# Intelligent_Agriculture.net
KiCad netlist of a schematic drawn in Altium Designer
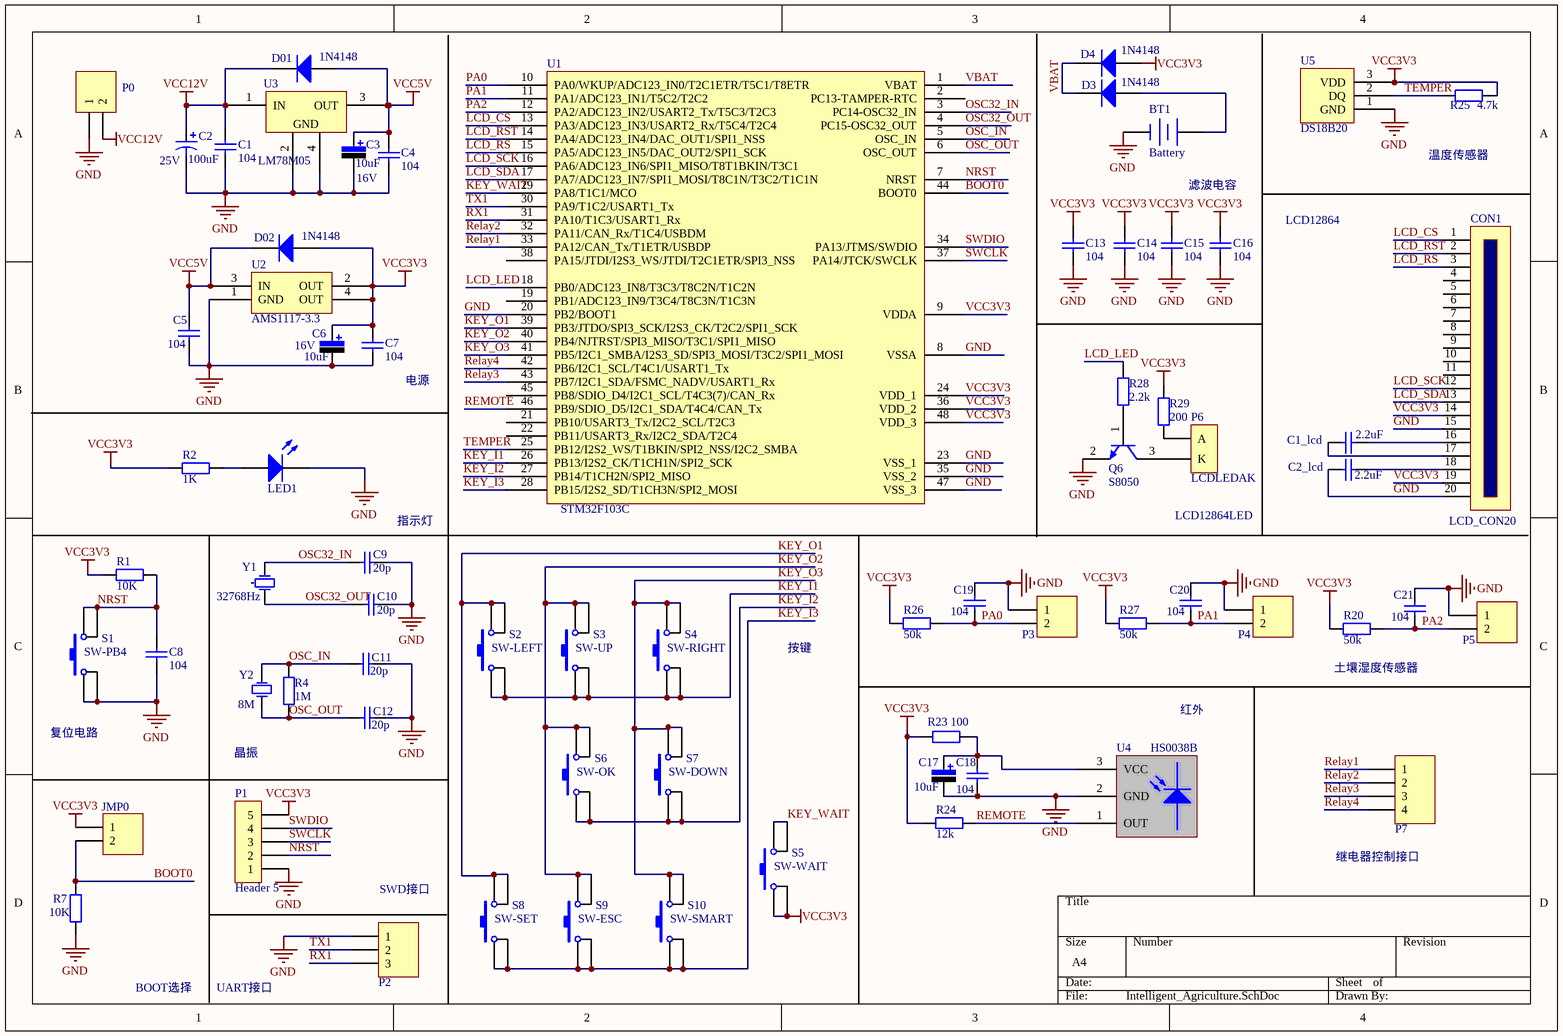
[diagram p0: Intelligent_Agriculture.SchDoc]

(export (version "E")
  (design (tool "Eeschema 10.0.6"))
  (components
    (comp (ref "BT1")
      (value "Battery")
      (footprint "CR1220")
      (description "备份电池")
      (fields (field (name "PUBLISHER") "Altium Limited"))
      (libsource (lib "fszhang") (part "Battery"))
    )
    (comp (ref "C1")
      (value "104")
      (footprint "C-RAD-0805")
      (description "无极性电容")
      (fields (field (name "Comment") "Cap") (field (name "PUBLISHER") "Altium Limited"))
      (libsource (lib "fszhang") (part "Cap"))
    )
    (comp (ref "C1_lcd")
      (value "2.2uF")
      (footprint "C-RAD-0805")
      (description "无极性电容")
      (fields (field (name "Comment") "Cap") (field (name "PUBLISHER") "Altium Limited"))
      (libsource (lib "fszhang") (part "Cap"))
    )
    (comp (ref "C2")
      (value "100uF")
      (footprint "C-RB-2.54")
      (description "电解电容")
      (fields
        (field (name "VOL") "25V")
        (field (name "Comment") "Cap Pol1")
        (field (name "PUBLISHER") "Altium Limited")
      )
      (libsource (lib "Miscellaneous Devices") (part "Cap Pol1"))
    )
    (comp (ref "C2_lcd")
      (value "2.2uF")
      (footprint "C-RAD-0805")
      (description "无极性电容")
      (fields (field (name "Comment") "Cap") (field (name "PUBLISHER") "Altium Limited"))
      (libsource (lib "fszhang") (part "Cap"))
    )
    (comp (ref "C3")
      (value "10uF")
      (footprint "CAP-3528")
      (description "钽电容")
      (fields
        (field (name "VOL") "16V")
        (field (name "Comment") "Cap Pol")
        (field (name "PUBLISHER") "Altium Limited")
      )
      (libsource (lib "fszhang") (part "Cap Pol"))
    )
    (comp (ref "C4")
      (value "104")
      (footprint "C-RAD-0805")
      (description "无极性电容")
      (fields (field (name "Comment") "Cap") (field (name "PUBLISHER") "Altium Limited"))
      (libsource (lib "fszhang") (part "Cap"))
    )
    (comp (ref "C5")
      (value "104")
      (footprint "C-RAD-0805")
      (description "无极性电容")
      (fields (field (name "Comment") "Cap") (field (name "PUBLISHER") "Altium Limited"))
      (libsource (lib "fszhang") (part "Cap"))
    )
    (comp (ref "C6")
      (value "10uF")
      (footprint "CAP-3528")
      (description "钽电容")
      (fields
        (field (name "VOL") "16V")
        (field (name "Comment") "Cap Pol")
        (field (name "PUBLISHER") "Altium Limited")
      )
      (libsource (lib "fszhang") (part "Cap Pol"))
    )
    (comp (ref "C7")
      (value "104")
      (footprint "C-RAD-0805")
      (description "无极性电容")
      (fields (field (name "Comment") "Cap") (field (name "PUBLISHER") "Altium Limited"))
      (libsource (lib "fszhang") (part "Cap"))
    )
    (comp (ref "C8")
      (value "104")
      (footprint "C-RAD-0805")
      (description "无极性电容")
      (fields (field (name "Comment") "Cap") (field (name "PUBLISHER") "Altium Limited"))
      (libsource (lib "fszhang") (part "Cap"))
    )
    (comp (ref "C9")
      (value "20p")
      (footprint "C-RAD-0805")
      (description "无极性电容")
      (fields (field (name "Comment") "Cap") (field (name "PUBLISHER") "Altium Limited"))
      (libsource (lib "fszhang") (part "Cap"))
    )
    (comp (ref "C10")
      (value "20p")
      (footprint "C-RAD-0805")
      (description "无极性电容")
      (fields (field (name "Comment") "Cap") (field (name "PUBLISHER") "Altium Limited"))
      (libsource (lib "fszhang") (part "Cap"))
    )
    (comp (ref "C11")
      (value "20p")
      (footprint "C-RAD-0805")
      (description "无极性电容")
      (fields (field (name "Comment") "Cap") (field (name "PUBLISHER") "Altium Limited"))
      (libsource (lib "fszhang") (part "Cap"))
    )
    (comp (ref "C12")
      (value "20p")
      (footprint "C-RAD-0805")
      (description "无极性电容")
      (fields (field (name "Comment") "Cap") (field (name "PUBLISHER") "Altium Limited"))
      (libsource (lib "fszhang") (part "Cap"))
    )
    (comp (ref "C13")
      (value "104")
      (footprint "C-RAD-0805")
      (description "无极性电容")
      (fields (field (name "Comment") "Cap") (field (name "PUBLISHER") "Altium Limited"))
      (libsource (lib "fszhang") (part "Cap"))
    )
    (comp (ref "C14")
      (value "104")
      (footprint "C-RAD-0805")
      (description "无极性电容")
      (fields (field (name "Comment") "Cap") (field (name "PUBLISHER") "Altium Limited"))
      (libsource (lib "fszhang") (part "Cap"))
    )
    (comp (ref "C15")
      (value "104")
      (footprint "C-RAD-0805")
      (description "无极性电容")
      (fields (field (name "Comment") "Cap") (field (name "PUBLISHER") "Altium Limited"))
      (libsource (lib "fszhang") (part "Cap"))
    )
    (comp (ref "C16")
      (value "104")
      (footprint "C-RAD-0805")
      (description "无极性电容")
      (fields (field (name "Comment") "Cap") (field (name "PUBLISHER") "Altium Limited"))
      (libsource (lib "fszhang") (part "Cap"))
    )
    (comp (ref "C17")
      (value "10uF")
      (footprint "CAP-3528")
      (description "钽电容")
      (fields (field (name "Comment") "Cap Pol") (field (name "PUBLISHER") "Altium Limited"))
      (libsource (lib "fszhang") (part "Cap Pol"))
    )
    (comp (ref "C18")
      (value "104")
      (footprint "C-RAD-0805")
      (description "无极性电容")
      (fields (field (name "Comment") "Cap") (field (name "PUBLISHER") "Altium Limited"))
      (libsource (lib "fszhang") (part "Cap"))
    )
    (comp (ref "C19")
      (value "104")
      (footprint "C-RAD-0805")
      (description "无极性电容")
      (fields (field (name "Comment") "Cap") (field (name "PUBLISHER") "Altium Limited"))
      (libsource (lib "fszhang") (part "Cap"))
    )
    (comp (ref "C20")
      (value "104")
      (footprint "C-RAD-0805")
      (description "无极性电容")
      (fields (field (name "Comment") "Cap") (field (name "PUBLISHER") "Altium Limited"))
      (libsource (lib "fszhang") (part "Cap"))
    )
    (comp (ref "C21")
      (value "104")
      (footprint "C-RAD-0805")
      (description "无极性电容")
      (fields (field (name "Comment") "Cap") (field (name "PUBLISHER") "Altium Limited"))
      (libsource (lib "fszhang") (part "Cap"))
    )
    (comp (ref "CON1")
      (value "LCD_CON20")
      (footprint "FPC0.5-20P-A")
      (description "LCD接插件")
      (libsource (lib "fszhang") (part "LCD_CON20"))
    )
    (comp (ref "D01")
      (value "1N4148")
      (footprint "DIODE-1206")
      (description "二极管")
      (fields (field (name "Comment") "Diode") (field (name "PUBLISHER") "Altium Limited"))
      (libsource (lib "fszhang") (part "Diode"))
    )
    (comp (ref "D02")
      (value "1N4148")
      (footprint "DIODE-1206")
      (description "二极管")
      (fields (field (name "Comment") "Diode") (field (name "PUBLISHER") "Altium Limited"))
      (libsource (lib "fszhang") (part "Diode"))
    )
    (comp (ref "D3")
      (value "1N4148")
      (footprint "DIODE-1206")
      (description "二极管")
      (fields (field (name "Comment") "Diode") (field (name "PUBLISHER") "Altium Limited"))
      (libsource (lib "fszhang") (part "Diode"))
    )
    (comp (ref "D4")
      (value "1N4148")
      (footprint "DIODE-1206")
      (description "二极管")
      (fields (field (name "Comment") "Diode") (field (name "PUBLISHER") "Altium Limited"))
      (libsource (lib "fszhang") (part "Diode"))
    )
    (comp (ref "JMP0")
      (value "Header 2")
      (footprint "HDR2X1_A")
      (description "接插件")
      (fields (field (name "PUBLISHER") "Altium Limited"))
      (libsource (lib "") (part "Header 2_1"))
    )
    (comp (ref "LED1")
      (value "LED0")
      (footprint "LED_A2")
      (description "发光二极管")
      (fields (field (name "PUBLISHER") "Altium Limited"))
      (libsource (lib "fszhang") (part "LED0"))
    )
    (comp (ref "P0")
      (value "Header 2")
      (footprint "HDR2X1_B1")
      (description "接插件")
      (fields (field (name "PUBLISHER") "Altium Limited"))
      (libsource (lib "fszhang") (part "Header 2"))
    )
    (comp (ref "P1")
      (value "Header 5")
      (footprint "HDR5_A1")
      (description "接插件")
      (fields (field (name "PUBLISHER") "Altium Limited"))
      (libsource (lib "fszhang") (part "Header 5"))
    )
    (comp (ref "P2")
      (value "Header 3")
      (footprint "HDR3X1_A")
      (description "接插件")
      (fields (field (name "PUBLISHER") "Altium Limited"))
      (libsource (lib "fszhang") (part "Header 3"))
    )
    (comp (ref "P3")
      (value "Header 2")
      (footprint "HDR2X1_B1")
      (description "接插件")
      (fields (field (name "PUBLISHER") "Altium Limited"))
      (libsource (lib "") (part "Header 2_1"))
    )
    (comp (ref "P4")
      (value "Header 2")
      (footprint "HDR2X1_B1")
      (description "接插件")
      (fields (field (name "PUBLISHER") "Altium Limited"))
      (libsource (lib "") (part "Header 2_1"))
    )
    (comp (ref "P5")
      (value "Header 2")
      (footprint "HDR2X1_B1")
      (description "接插件")
      (fields (field (name "PUBLISHER") "Altium Limited"))
      (libsource (lib "") (part "Header 2_1"))
    )
    (comp (ref "P6")
      (value "LCDLEDAK")
      (footprint "LCD_JLX12864G-1504")
      (description "LCD12864框架")
      (libsource (lib "fszhang") (part "LCDLEDAK"))
    )
    (comp (ref "P7")
      (value "Header 4")
      (footprint "HDR4X1_B1")
      (description "接插件")
      (fields (field (name "PUBLISHER") "Altium Limited"))
      (libsource (lib "fszhang") (part "Header 4"))
    )
    (comp (ref "Q6")
      (value "S8050")
      (footprint "SOT-23")
      (description "NPN三极管")
      (fields (field (name "PUBLISHER") "Altium Limited"))
      (libsource (lib "fszhang") (part "BCP68"))
    )
    (comp (ref "R1")
      (value "10K")
      (footprint "0805-1")
      (description "贴片电阻")
      (fields (field (name "Comment") "Res1") (field (name "PUBLISHER") "Altium Limited"))
      (libsource (lib "") (part "Res1_3"))
    )
    (comp (ref "R2")
      (value "1K")
      (footprint "0805-1")
      (description "贴片电阻")
      (fields (field (name "Comment") "Res1") (field (name "PUBLISHER") "Altium Limited"))
      (libsource (lib "") (part "Res1_2"))
    )
    (comp (ref "R4")
      (value "1M")
      (footprint "0805-1")
      (description "贴片电阻")
      (fields (field (name "Comment") "Res1") (field (name "PUBLISHER") "Altium Limited"))
      (libsource (lib "fszhang") (part "Res1"))
    )
    (comp (ref "R7")
      (value "10K")
      (footprint "0805-1")
      (description "贴片电阻")
      (fields (field (name "Comment") "Res1") (field (name "PUBLISHER") "Altium Limited"))
      (libsource (lib "") (part "Res1_1"))
    )
    (comp (ref "R20")
      (value "50k")
      (footprint "0805-1")
      (description "贴片电阻")
      (fields (field (name "Comment") "Res1") (field (name "PUBLISHER") "Altium Limited"))
      (libsource (lib "") (part "Res1_3"))
    )
    (comp (ref "R23")
      (value "100")
      (footprint "0805-1")
      (description "贴片电阻")
      (fields (field (name "Comment") "Res1") (field (name "PUBLISHER") "Altium Limited"))
      (libsource (lib "") (part "Res1_2"))
    )
    (comp (ref "R24")
      (value "12k")
      (footprint "0805-1")
      (description "贴片电阻")
      (fields (field (name "Comment") "Res1") (field (name "PUBLISHER") "Altium Limited"))
      (libsource (lib "") (part "Res1_2"))
    )
    (comp (ref "R25")
      (value "4.7k")
      (footprint "0805-1")
      (description "贴片电阻")
      (fields (field (name "Comment") "Res1") (field (name "PUBLISHER") "Altium Limited"))
      (libsource (lib "") (part "Res1_2"))
    )
    (comp (ref "R26")
      (value "50k")
      (footprint "0805-1")
      (description "贴片电阻")
      (fields (field (name "Comment") "Res1") (field (name "PUBLISHER") "Altium Limited"))
      (libsource (lib "") (part "Res1_3"))
    )
    (comp (ref "R27")
      (value "50k")
      (footprint "0805-1")
      (description "贴片电阻")
      (fields (field (name "Comment") "Res1") (field (name "PUBLISHER") "Altium Limited"))
      (libsource (lib "") (part "Res1_3"))
    )
    (comp (ref "R28")
      (value "2.2k")
      (footprint "0805-1")
      (description "贴片电阻")
      (fields (field (name "Comment") "Res1") (field (name "PUBLISHER") "Altium Limited"))
      (libsource (lib "fszhang") (part "Res1"))
    )
    (comp (ref "R29")
      (value "200")
      (footprint "1206")
      (description "贴片电阻")
      (fields (field (name "Comment") "Res1") (field (name "PUBLISHER") "Altium Limited"))
      (libsource (lib "fszhang") (part "Res1"))
    )
    (comp (ref "S1")
      (value "SW-PB4")
      (footprint "SW_PB4_B1")
      (description "微动开关")
      (fields (field (name "PUBLISHER") "Altium Limited"))
      (libsource (lib "fszhang") (part "SW-PB4"))
    )
    (comp (ref "S2")
      (value "SW-LEFT")
      (footprint "SW_PB4_B1")
      (description "微动开关")
      (fields (field (name "PUBLISHER") "Altium Limited"))
      (libsource (lib "fszhang") (part "SW-PB4"))
    )
    (comp (ref "S3")
      (value "SW-UP")
      (footprint "SW_PB4_B1")
      (description "微动开关")
      (fields (field (name "PUBLISHER") "Altium Limited"))
      (libsource (lib "fszhang") (part "SW-PB4"))
    )
    (comp (ref "S4")
      (value "SW-RIGHT")
      (footprint "SW_PB4_B1")
      (description "微动开关")
      (fields (field (name "PUBLISHER") "Altium Limited"))
      (libsource (lib "fszhang") (part "SW-PB4"))
    )
    (comp (ref "S5")
      (value "SW-WAIT")
      (footprint "SW_PB4_B1")
      (description "微动开关")
      (fields (field (name "PUBLISHER") "Altium Limited"))
      (libsource (lib "fszhang") (part "SW-PB4"))
    )
    (comp (ref "S6")
      (value "SW-OK")
      (footprint "SW_PB4_B1")
      (description "微动开关")
      (fields (field (name "PUBLISHER") "Altium Limited"))
      (libsource (lib "fszhang") (part "SW-PB4"))
    )
    (comp (ref "S7")
      (value "SW-DOWN")
      (footprint "SW_PB4_B1")
      (description "微动开关")
      (fields (field (name "PUBLISHER") "Altium Limited"))
      (libsource (lib "fszhang") (part "SW-PB4"))
    )
    (comp (ref "S8")
      (value "SW-SET")
      (footprint "SW_PB4_B1")
      (description "微动开关")
      (fields (field (name "PUBLISHER") "Altium Limited"))
      (libsource (lib "fszhang") (part "SW-PB4"))
    )
    (comp (ref "S9")
      (value "SW-ESC")
      (footprint "SW_PB4_B1")
      (description "微动开关")
      (fields (field (name "PUBLISHER") "Altium Limited"))
      (libsource (lib "fszhang") (part "SW-PB4"))
    )
    (comp (ref "S10")
      (value "SW-SMART")
      (footprint "SW_PB4_B1")
      (description "微动开关")
      (fields (field (name "PUBLISHER") "Altium Limited"))
      (libsource (lib "fszhang") (part "SW-PB4"))
    )
    (comp (ref "U1")
      (value "STM32F103C")
      (footprint "LQFP-48_M")
      (description "STM32单片机48引脚")
      (libsource (lib "fszhang") (part "STM32F103C"))
    )
    (comp (ref "U2")
      (value "AMS1117-3.3")
      (footprint "SOT-223")
      (description "3.3V稳压芯片")
      (libsource (lib "fszhang") (part "SPX1117M3-3.3"))
    )
    (comp (ref "U3")
      (value "LM78M05")
      (footprint "TO-252")
      (description "5V稳压芯片")
      (libsource (lib "fszhang") (part "LM78M05"))
    )
    (comp (ref "U4")
      (value "HS0038B")
      (footprint "HS0038B")
      (description "红外接收器")
      (libsource (lib "fszhang") (part "HS0038B"))
    )
    (comp (ref "U5")
      (value "DS18B20")
      (footprint "HDR3X1_B1")
      (description "温度传感器")
      (libsource (lib "fszhang") (part "DS18B20"))
    )
    (comp (ref "Y1")
      (value "32768Hz")
      (footprint "X-TC15_B")
      (description "圆柱晶振")
      (fields (field (name "Comment") "XTAL_SM") (field (name "PUBLISHER") "Altium Limited"))
      (libsource (lib "fszhang") (part "XTAL_SM"))
    )
    (comp (ref "Y2")
      (value "8M")
      (footprint "X-HC49U")
      (description "晶振")
      (fields (field (name "Comment") "XTAL") (field (name "PUBLISHER") "Altium Limited"))
      (libsource (lib "fszhang") (part "XTAL"))
    )
  )
  (nets
    (net (code "1") (name "/BOOT0") (class "Default")
      (node (ref "JMP0") (pin "2") (pinfunction "2_2") (pintype "passive"))
      (node (ref "R7") (pin "1") (pinfunction "1_1") (pintype "passive"))
      (node (ref "U1") (pin "44") (pinfunction "BOOT0_44") (pintype "passive"))
    )
    (net (code "2") (name "/KEY_I1") (class "Default")
      (node (ref "S2") (pin "1") (pinfunction "1_1") (pintype "passive"))
      (node (ref "S2") (pin "4") (pinfunction "4_4") (pintype "passive"))
      (node (ref "S3") (pin "1") (pinfunction "1_1") (pintype "passive"))
      (node (ref "S3") (pin "4") (pinfunction "4_4") (pintype "passive"))
      (node (ref "S4") (pin "1") (pinfunction "1_1") (pintype "passive"))
      (node (ref "S4") (pin "4") (pinfunction "4_4") (pintype "passive"))
      (node (ref "U1") (pin "26") (pinfunction "PB13/I2S2_CK/T1CH1N/SPI2_SCK_26") (pintype "passive"))
    )
    (net (code "3") (name "/KEY_I2") (class "Default")
      (node (ref "S6") (pin "1") (pinfunction "1_1") (pintype "passive"))
      (node (ref "S6") (pin "4") (pinfunction "4_4") (pintype "passive"))
      (node (ref "S7") (pin "1") (pinfunction "1_1") (pintype "passive"))
      (node (ref "S7") (pin "4") (pinfunction "4_4") (pintype "passive"))
      (node (ref "U1") (pin "27") (pinfunction "PB14/T1CH2N/SPI2_MISO_27") (pintype "passive"))
    )
    (net (code "4") (name "/KEY_I3") (class "Default")
      (node (ref "S10") (pin "1") (pinfunction "1_1") (pintype "passive"))
      (node (ref "S10") (pin "4") (pinfunction "4_4") (pintype "passive"))
      (node (ref "S8") (pin "1") (pinfunction "1_1") (pintype "passive"))
      (node (ref "S8") (pin "4") (pinfunction "4_4") (pintype "passive"))
      (node (ref "S9") (pin "1") (pinfunction "1_1") (pintype "passive"))
      (node (ref "S9") (pin "4") (pinfunction "4_4") (pintype "passive"))
      (node (ref "U1") (pin "28") (pinfunction "PB15/I2S2_SD/T1CH3N/SPI2_MOSI_28") (pintype "passive"))
    )
    (net (code "5") (name "/KEY_O1") (class "Default")
      (node (ref "S2") (pin "2") (pinfunction "2_2") (pintype "passive"))
      (node (ref "S2") (pin "3") (pinfunction "3_3") (pintype "passive"))
      (node (ref "S8") (pin "2") (pinfunction "2_2") (pintype "passive"))
      (node (ref "S8") (pin "3") (pinfunction "3_3") (pintype "passive"))
      (node (ref "U1") (pin "39") (pinfunction "PB3/JTDO/SPI3_SCK/I2S3_CK/T2C2/SPI1_SCK_39") (pintype "passive"))
    )
    (net (code "6") (name "/KEY_O2") (class "Default")
      (node (ref "S3") (pin "2") (pinfunction "2_2") (pintype "passive"))
      (node (ref "S3") (pin "3") (pinfunction "3_3") (pintype "passive"))
      (node (ref "S6") (pin "2") (pinfunction "2_2") (pintype "passive"))
      (node (ref "S6") (pin "3") (pinfunction "3_3") (pintype "passive"))
      (node (ref "S9") (pin "2") (pinfunction "2_2") (pintype "passive"))
      (node (ref "S9") (pin "3") (pinfunction "3_3") (pintype "passive"))
      (node (ref "U1") (pin "40") (pinfunction "PB4/NJTRST/SPI3_MISO/T3C1/SPI1_MISO_40") (pintype "passive"))
    )
    (net (code "7") (name "/KEY_O3") (class "Default")
      (node (ref "S10") (pin "2") (pinfunction "2_2") (pintype "passive"))
      (node (ref "S10") (pin "3") (pinfunction "3_3") (pintype "passive"))
      (node (ref "S4") (pin "2") (pinfunction "2_2") (pintype "passive"))
      (node (ref "S4") (pin "3") (pinfunction "3_3") (pintype "passive"))
      (node (ref "S7") (pin "2") (pinfunction "2_2") (pintype "passive"))
      (node (ref "S7") (pin "3") (pinfunction "3_3") (pintype "passive"))
      (node (ref "U1") (pin "41") (pinfunction "PB5/I2C1_SMBA/I2S3_SD/SPI3_MOSI/T3C2/SPI1_MOSI_41") (pintype "passive"))
    )
    (net (code "8") (name "/KEY_WAIT") (class "Default")
      (node (ref "S5") (pin "2") (pinfunction "2_2") (pintype "passive"))
      (node (ref "S5") (pin "3") (pinfunction "3_3") (pintype "passive"))
      (node (ref "U1") (pin "29") (pinfunction "PA8/T1C1/MCO_29") (pintype "passive"))
    )
    (net (code "9") (name "/LCD_CS") (class "Default")
      (node (ref "CON1") (pin "1") (pinfunction "1_1") (pintype "passive"))
      (node (ref "U1") (pin "13") (pinfunction "PA3/ADC123_IN3/USART2_Rx/T5C4/T2C4_13") (pintype "passive"))
    )
    (net (code "10") (name "/LCD_LED") (class "Default")
      (node (ref "R28") (pin "2") (pinfunction "2_2") (pintype "passive"))
      (node (ref "U1") (pin "18") (pinfunction "PB0/ADC123_IN8/T3C3/T8C2N/T1C2N_18") (pintype "passive"))
    )
    (net (code "11") (name "/LCD_RS") (class "Default")
      (node (ref "CON1") (pin "3") (pinfunction "3_3") (pintype "passive"))
      (node (ref "U1") (pin "15") (pinfunction "PA5/ADC123_IN5/DAC_OUT2/SPI1_SCK_15") (pintype "passive"))
    )
    (net (code "12") (name "/LCD_RST") (class "Default")
      (node (ref "CON1") (pin "2") (pinfunction "2_2") (pintype "passive"))
      (node (ref "U1") (pin "14") (pinfunction "PA4/ADC123_IN4/DAC_OUT1/SPI1_NSS_14") (pintype "passive"))
    )
    (net (code "13") (name "/LCD_SCK") (class "Default")
      (node (ref "CON1") (pin "12") (pinfunction "12_12") (pintype "passive"))
      (node (ref "U1") (pin "16") (pinfunction "PA6/ADC123_IN6/SPI1_MISO/T8T1BKIN/T3C1_16") (pintype "passive"))
    )
    (net (code "14") (name "/LCD_SDA") (class "Default")
      (node (ref "CON1") (pin "13") (pinfunction "13_13") (pintype "passive"))
      (node (ref "U1") (pin "17") (pinfunction "PA7/ADC123_IN7/SPI1_MOSI/T8C1N/T3C2/T1C1N_17") (pintype "passive"))
    )
    (net (code "15") (name "/NRST") (class "Default")
      (node (ref "C8") (pin "1") (pinfunction "1_1") (pintype "passive"))
      (node (ref "P1") (pin "2") (pinfunction "2_2") (pintype "passive"))
      (node (ref "R1") (pin "1") (pinfunction "1_1") (pintype "passive"))
      (node (ref "S1") (pin "2") (pinfunction "2_2") (pintype "passive"))
      (node (ref "S1") (pin "3") (pinfunction "3_3") (pintype "passive"))
      (node (ref "U1") (pin "7") (pinfunction "NRST_7") (pintype "passive"))
    )
    (net (code "16") (name "/OSC32_IN") (class "Default")
      (node (ref "C9") (pin "1") (pinfunction "1_1") (pintype "passive"))
      (node (ref "U1") (pin "3") (pinfunction "PC14-OSC32_IN_3") (pintype "passive"))
      (node (ref "Y1") (pin "1") (pinfunction "OSC1_1") (pintype "passive"))
    )
    (net (code "17") (name "/OSC32_OUT") (class "Default")
      (node (ref "C10") (pin "1") (pinfunction "1_1") (pintype "passive"))
      (node (ref "U1") (pin "4") (pinfunction "PC15-OSC32_OUT_4") (pintype "passive"))
      (node (ref "Y1") (pin "2") (pinfunction "OSC2_2") (pintype "passive"))
    )
    (net (code "18") (name "/OSC_IN") (class "Default")
      (node (ref "C11") (pin "1") (pinfunction "1_1") (pintype "passive"))
      (node (ref "R4") (pin "2") (pinfunction "2_2") (pintype "passive"))
      (node (ref "U1") (pin "5") (pinfunction "OSC_IN_5") (pintype "passive"))
      (node (ref "Y2") (pin "2") (pinfunction "OSC2_2") (pintype "passive"))
    )
    (net (code "19") (name "/OSC_OUT") (class "Default")
      (node (ref "C12") (pin "1") (pinfunction "1_1") (pintype "passive"))
      (node (ref "R4") (pin "1") (pinfunction "1_1") (pintype "passive"))
      (node (ref "U1") (pin "6") (pinfunction "OSC_OUT_6") (pintype "passive"))
      (node (ref "Y2") (pin "1") (pinfunction "OSC1_1") (pintype "passive"))
    )
    (net (code "20") (name "/PA0") (class "Default")
      (node (ref "C19") (pin "2") (pinfunction "2_2") (pintype "passive"))
      (node (ref "P3") (pin "2") (pinfunction "2_2") (pintype "passive"))
      (node (ref "R26") (pin "1") (pinfunction "1_1") (pintype "passive"))
      (node (ref "U1") (pin "10") (pinfunction "PA0/WKUP/ADC123_IN0/T2C1ETR/T5C1/T8ETR_10") (pintype "passive"))
    )
    (net (code "21") (name "/PA1") (class "Default")
      (node (ref "C20") (pin "2") (pinfunction "2_2") (pintype "passive"))
      (node (ref "P4") (pin "2") (pinfunction "2_2") (pintype "passive"))
      (node (ref "R27") (pin "1") (pinfunction "1_1") (pintype "passive"))
      (node (ref "U1") (pin "11") (pinfunction "PA1/ADC123_IN1/T5C2/T2C2_11") (pintype "passive"))
    )
    (net (code "22") (name "/PA2") (class "Default")
      (node (ref "C21") (pin "2") (pinfunction "2_2") (pintype "passive"))
      (node (ref "P5") (pin "2") (pinfunction "2_2") (pintype "passive"))
      (node (ref "R20") (pin "1") (pinfunction "1_1") (pintype "passive"))
      (node (ref "U1") (pin "12") (pinfunction "PA2/ADC123_IN2/USART2_Tx/T5C3/T2C3_12") (pintype "passive"))
    )
    (net (code "23") (name "/REMOTE") (class "Default")
      (node (ref "R24") (pin "2") (pinfunction "2_2") (pintype "passive"))
      (node (ref "U1") (pin "46") (pinfunction "PB9/SDIO_D5/I2C1_SDA/T4C4/CAN_Tx_46") (pintype "passive"))
      (node (ref "U4") (pin "1") (pinfunction "OUT_1") (pintype "passive"))
    )
    (net (code "24") (name "/RX1") (class "Default")
      (node (ref "P2") (pin "3") (pinfunction "3_3") (pintype "passive"))
      (node (ref "U1") (pin "31") (pinfunction "PA10/T1C3/USART1_Rx_31") (pintype "passive"))
    )
    (net (code "25") (name "/Relay1") (class "Default")
      (node (ref "P7") (pin "1") (pinfunction "1_1") (pintype "passive"))
      (node (ref "U1") (pin "33") (pinfunction "PA12/CAN_Tx/T1ETR/USBDP_33") (pintype "passive"))
    )
    (net (code "26") (name "/Relay2") (class "Default")
      (node (ref "P7") (pin "2") (pinfunction "2_2") (pintype "passive"))
      (node (ref "U1") (pin "32") (pinfunction "PA11/CAN_Rx/T1C4/USBDM_32") (pintype "passive"))
    )
    (net (code "27") (name "/Relay3") (class "Default")
      (node (ref "P7") (pin "3") (pinfunction "3_3") (pintype "passive"))
      (node (ref "U1") (pin "43") (pinfunction "PB7/I2C1_SDA/FSMC_NADV/USART1_Rx_43") (pintype "passive"))
    )
    (net (code "28") (name "/Relay4") (class "Default")
      (node (ref "P7") (pin "4") (pinfunction "4_4") (pintype "passive"))
      (node (ref "U1") (pin "42") (pinfunction "PB6/I2C1_SCL/T4C1/USART1_Tx_42") (pintype "passive"))
    )
    (net (code "29") (name "/SWCLK") (class "Default")
      (node (ref "P1") (pin "3") (pinfunction "3_3") (pintype "passive"))
      (node (ref "U1") (pin "37") (pinfunction "PA14/JTCK/SWCLK_37") (pintype "passive"))
    )
    (net (code "30") (name "/SWDIO") (class "Default")
      (node (ref "P1") (pin "4") (pinfunction "4_4") (pintype "passive"))
      (node (ref "U1") (pin "34") (pinfunction "PA13/JTMS/SWDIO_34") (pintype "passive"))
    )
    (net (code "31") (name "/TEMPER") (class "Default")
      (node (ref "R25") (pin "1") (pinfunction "1_1") (pintype "passive"))
      (node (ref "U1") (pin "25") (pinfunction "PB12/I2S2_WS/T1BKIN/SPI2_NSS/I2C2_SMBA_25") (pintype "passive"))
      (node (ref "U5") (pin "2") (pinfunction "DQ_2") (pintype "passive"))
    )
    (net (code "32") (name "/TX1") (class "Default")
      (node (ref "P2") (pin "2") (pinfunction "2_2") (pintype "passive"))
      (node (ref "U1") (pin "30") (pinfunction "PA9/T1C2/USART1_Tx_30") (pintype "passive"))
    )
    (net (code "33") (name "/VBAT") (class "Default")
      (node (ref "D3") (pin "2") (pinfunction "K_2") (pintype "passive"))
      (node (ref "D4") (pin "2") (pinfunction "K_2") (pintype "passive"))
      (node (ref "U1") (pin "1") (pinfunction "VBAT_1") (pintype "passive"))
    )
    (net (code "34") (name "GND") (class "Default")
      (node (ref "BT1") (pin "2") (pinfunction "-_2") (pintype "passive"))
      (node (ref "C1") (pin "2") (pinfunction "2_2") (pintype "passive"))
      (node (ref "C10") (pin "2") (pinfunction "2_2") (pintype "passive"))
      (node (ref "C11") (pin "2") (pinfunction "2_2") (pintype "passive"))
      (node (ref "C12") (pin "2") (pinfunction "2_2") (pintype "passive"))
      (node (ref "C13") (pin "2") (pinfunction "2_2") (pintype "passive"))
      (node (ref "C14") (pin "2") (pinfunction "2_2") (pintype "passive"))
      (node (ref "C15") (pin "2") (pinfunction "2_2") (pintype "passive"))
      (node (ref "C16") (pin "2") (pinfunction "2_2") (pintype "passive"))
      (node (ref "C17") (pin "2") (pinfunction "2_2") (pintype "passive"))
      (node (ref "C18") (pin "2") (pinfunction "2_2") (pintype "passive"))
      (node (ref "C19") (pin "1") (pinfunction "1_1") (pintype "passive"))
      (node (ref "C2") (pin "2") (pinfunction "2_2") (pintype "passive"))
      (node (ref "C20") (pin "1") (pinfunction "1_1") (pintype "passive"))
      (node (ref "C21") (pin "1") (pinfunction "1_1") (pintype "passive"))
      (node (ref "C2_lcd") (pin "2") (pinfunction "2_2") (pintype "passive"))
      (node (ref "C3") (pin "2") (pinfunction "2_2") (pintype "passive"))
      (node (ref "C4") (pin "2") (pinfunction "2_2") (pintype "passive"))
      (node (ref "C5") (pin "2") (pinfunction "2_2") (pintype "passive"))
      (node (ref "C6") (pin "2") (pinfunction "2_2") (pintype "passive"))
      (node (ref "C7") (pin "2") (pinfunction "2_2") (pintype "passive"))
      (node (ref "C8") (pin "2") (pinfunction "2_2") (pintype "passive"))
      (node (ref "C9") (pin "2") (pinfunction "2_2") (pintype "passive"))
      (node (ref "CON1") (pin "15") (pinfunction "15_15") (pintype "passive"))
      (node (ref "CON1") (pin "20") (pinfunction "20_20") (pintype "passive"))
      (node (ref "LED1") (pin "2") (pinfunction "K_2") (pintype "passive"))
      (node (ref "P0") (pin "1") (pinfunction "1_1") (pintype "passive"))
      (node (ref "P1") (pin "1") (pinfunction "1_1") (pintype "passive"))
      (node (ref "P2") (pin "1") (pinfunction "1_1") (pintype "passive"))
      (node (ref "P3") (pin "1") (pinfunction "1_1") (pintype "passive"))
      (node (ref "P4") (pin "1") (pinfunction "1_1") (pintype "passive"))
      (node (ref "P5") (pin "1") (pinfunction "1_1") (pintype "passive"))
      (node (ref "Q6") (pin "2") (pinfunction "E_2") (pintype "passive"))
      (node (ref "R7") (pin "2") (pinfunction "2_2") (pintype "passive"))
      (node (ref "S1") (pin "1") (pinfunction "1_1") (pintype "passive"))
      (node (ref "S1") (pin "4") (pinfunction "4_4") (pintype "passive"))
      (node (ref "U1") (pin "20") (pinfunction "PB2/BOOT1_20") (pintype "passive"))
      (node (ref "U1") (pin "23") (pinfunction "VSS_1_23") (pintype "passive"))
      (node (ref "U1") (pin "35") (pinfunction "VSS_2_35") (pintype "passive"))
      (node (ref "U1") (pin "47") (pinfunction "VSS_3_47") (pintype "passive"))
      (node (ref "U1") (pin "8") (pinfunction "VSSA_8") (pintype "passive"))
      (node (ref "U2") (pin "1") (pinfunction "GND_1") (pintype "passive"))
      (node (ref "U3") (pin "2") (pinfunction "GND_2") (pintype "power_in"))
      (node (ref "U3") (pin "4") (pinfunction "GND_4") (pintype "power_in"))
      (node (ref "U4") (pin "2") (pinfunction "GND_2") (pintype "passive"))
      (node (ref "U5") (pin "1") (pinfunction "GND_1") (pintype "passive"))
    )
    (net (code "35") (name "Net-(BT1-+)") (class "Default")
      (node (ref "BT1") (pin "1") (pinfunction "+_1") (pintype "passive"))
      (node (ref "D3") (pin "1") (pinfunction "A_1") (pintype "passive"))
    )
    (net (code "36") (name "Net-(C1_lcd-Pad1)") (class "Default")
      (node (ref "C1_lcd") (pin "1") (pinfunction "1_1") (pintype "passive"))
      (node (ref "CON1") (pin "16") (pinfunction "16_16") (pintype "passive"))
    )
    (net (code "37") (name "Net-(C1_lcd-Pad2)") (class "Default")
      (node (ref "C1_lcd") (pin "2") (pinfunction "2_2") (pintype "passive"))
      (node (ref "CON1") (pin "17") (pinfunction "17_17") (pintype "passive"))
    )
    (net (code "38") (name "Net-(C2_lcd-Pad1)") (class "Default")
      (node (ref "C2_lcd") (pin "1") (pinfunction "1_1") (pintype "passive"))
      (node (ref "CON1") (pin "18") (pinfunction "18_18") (pintype "passive"))
    )
    (net (code "39") (name "Net-(LED1-A)") (class "Default")
      (node (ref "LED1") (pin "1") (pinfunction "A_1") (pintype "passive"))
      (node (ref "R2") (pin "2") (pinfunction "2_2") (pintype "passive"))
    )
    (net (code "40") (name "Net-(P6-A)") (class "Default")
      (node (ref "P6") (pin "1") (pinfunction "A_1") (pintype "passive"))
      (node (ref "R29") (pin "1") (pinfunction "1_1") (pintype "passive"))
    )
    (net (code "41") (name "Net-(P6-K)") (class "Default")
      (node (ref "P6") (pin "2") (pinfunction "K_2") (pintype "passive"))
      (node (ref "Q6") (pin "3") (pinfunction "C_3") (pintype "passive"))
    )
    (net (code "42") (name "Net-(Q6-B)") (class "Default")
      (node (ref "Q6") (pin "1") (pinfunction "B_1") (pintype "passive"))
      (node (ref "R28") (pin "1") (pinfunction "1_1") (pintype "passive"))
    )
    (net (code "43") (name "Net-(U4-VCC)") (class "Default")
      (node (ref "C17") (pin "1") (pinfunction "1_1") (pintype "passive"))
      (node (ref "C18") (pin "1") (pinfunction "1_1") (pintype "passive"))
      (node (ref "R23") (pin "2") (pinfunction "2_2") (pintype "passive"))
      (node (ref "U4") (pin "3") (pinfunction "VCC_3") (pintype "passive"))
    )
    (net (code "44") (name "VCC3V3") (class "Default")
      (node (ref "C13") (pin "1") (pinfunction "1_1") (pintype "passive"))
      (node (ref "C14") (pin "1") (pinfunction "1_1") (pintype "passive"))
      (node (ref "C15") (pin "1") (pinfunction "1_1") (pintype "passive"))
      (node (ref "C16") (pin "1") (pinfunction "1_1") (pintype "passive"))
      (node (ref "C6") (pin "1") (pinfunction "1_1") (pintype "passive"))
      (node (ref "C7") (pin "1") (pinfunction "1_1") (pintype "passive"))
      (node (ref "CON1") (pin "14") (pinfunction "14_14") (pintype "passive"))
      (node (ref "CON1") (pin "19") (pinfunction "19_19") (pintype "passive"))
      (node (ref "D02") (pin "1") (pinfunction "A_1") (pintype "passive"))
      (node (ref "D4") (pin "1") (pinfunction "A_1") (pintype "passive"))
      (node (ref "JMP0") (pin "1") (pinfunction "1_1") (pintype "passive"))
      (node (ref "P1") (pin "5") (pinfunction "5_5") (pintype "passive"))
      (node (ref "R1") (pin "2") (pinfunction "2_2") (pintype "passive"))
      (node (ref "R2") (pin "1") (pinfunction "1_1") (pintype "passive"))
      (node (ref "R20") (pin "2") (pinfunction "2_2") (pintype "passive"))
      (node (ref "R23") (pin "1") (pinfunction "1_1") (pintype "passive"))
      (node (ref "R24") (pin "1") (pinfunction "1_1") (pintype "passive"))
      (node (ref "R25") (pin "2") (pinfunction "2_2") (pintype "passive"))
      (node (ref "R26") (pin "2") (pinfunction "2_2") (pintype "passive"))
      (node (ref "R27") (pin "2") (pinfunction "2_2") (pintype "passive"))
      (node (ref "R29") (pin "2") (pinfunction "2_2") (pintype "passive"))
      (node (ref "S5") (pin "1") (pinfunction "1_1") (pintype "passive"))
      (node (ref "S5") (pin "4") (pinfunction "4_4") (pintype "passive"))
      (node (ref "U1") (pin "24") (pinfunction "VDD_1_24") (pintype "passive"))
      (node (ref "U1") (pin "36") (pinfunction "VDD_2_36") (pintype "passive"))
      (node (ref "U1") (pin "48") (pinfunction "VDD_3_48") (pintype "passive"))
      (node (ref "U1") (pin "9") (pinfunction "VDDA_9") (pintype "passive"))
      (node (ref "U2") (pin "2") (pinfunction "OUT_2") (pintype "passive"))
      (node (ref "U2") (pin "4") (pinfunction "OUT_4") (pintype "passive"))
      (node (ref "U5") (pin "3") (pinfunction "VDD_3") (pintype "passive"))
    )
    (net (code "45") (name "VCC5V") (class "Default")
      (node (ref "C3") (pin "1") (pinfunction "1_1") (pintype "passive"))
      (node (ref "C4") (pin "1") (pinfunction "1_1") (pintype "passive"))
      (node (ref "C5") (pin "1") (pinfunction "1_1") (pintype "passive"))
      (node (ref "D01") (pin "1") (pinfunction "A_1") (pintype "passive"))
      (node (ref "D02") (pin "2") (pinfunction "K_2") (pintype "passive"))
      (node (ref "U2") (pin "3") (pinfunction "IN_3") (pintype "passive"))
      (node (ref "U3") (pin "3") (pinfunction "OUT_3") (pintype "power_in"))
    )
    (net (code "46") (name "VCC12V") (class "Default")
      (node (ref "C1") (pin "1") (pinfunction "1_1") (pintype "passive"))
      (node (ref "C2") (pin "1") (pinfunction "1_1") (pintype "passive"))
      (node (ref "D01") (pin "2") (pinfunction "K_2") (pintype "passive"))
      (node (ref "P0") (pin "2") (pinfunction "2_2") (pintype "passive"))
      (node (ref "U3") (pin "1") (pinfunction "IN_1") (pintype "power_in"))
    )
    (net (code "47") (name "unconnected-(CON1-Pad4)") (class "Default")
      (node (ref "CON1") (pin "4") (pinfunction "4_4") (pintype "passive"))
    )
    (net (code "48") (name "unconnected-(CON1-Pad5)") (class "Default")
      (node (ref "CON1") (pin "5") (pinfunction "5_5") (pintype "passive"))
    )
    (net (code "49") (name "unconnected-(CON1-Pad6)") (class "Default")
      (node (ref "CON1") (pin "6") (pinfunction "6_6") (pintype "passive"))
    )
    (net (code "50") (name "unconnected-(CON1-Pad7)") (class "Default")
      (node (ref "CON1") (pin "7") (pinfunction "7_7") (pintype "passive"))
    )
    (net (code "51") (name "unconnected-(CON1-Pad8)") (class "Default")
      (node (ref "CON1") (pin "8") (pinfunction "8_8") (pintype "passive"))
    )
    (net (code "52") (name "unconnected-(CON1-Pad9)") (class "Default")
      (node (ref "CON1") (pin "9") (pinfunction "9_9") (pintype "passive"))
    )
    (net (code "53") (name "unconnected-(CON1-Pad10)") (class "Default")
      (node (ref "CON1") (pin "10") (pinfunction "10_10") (pintype "passive"))
    )
    (net (code "54") (name "unconnected-(CON1-Pad11)") (class "Default")
      (node (ref "CON1") (pin "11") (pinfunction "11_11") (pintype "passive"))
    )
    (net (code "55") (name "unconnected-(U1-PA15{slash}JTDI{slash}I2S3_WS{slash}JTDI{slash}T2C1ETR{slash}SPI3_NSS-Pad38)") (class "Default")
      (node (ref "U1") (pin "38") (pinfunction "PA15/JTDI/I2S3_WS/JTDI/T2C1ETR/SPI3_NSS_38") (pintype "passive"))
    )
    (net (code "56") (name "unconnected-(U1-PB1{slash}ADC123_IN9{slash}T3C4{slash}T8C3N{slash}T1C3N-Pad19)") (class "Default")
      (node (ref "U1") (pin "19") (pinfunction "PB1/ADC123_IN9/T3C4/T8C3N/T1C3N_19") (pintype "passive"))
    )
    (net (code "57") (name "unconnected-(U1-PB8{slash}SDIO_D4{slash}I2C1_SCL{slash}T4C3(7){slash}CAN_Rx-Pad45)") (class "Default")
      (node (ref "U1") (pin "45") (pinfunction "PB8/SDIO_D4/I2C1_SCL/T4C3(7)/CAN_Rx_45") (pintype "passive"))
    )
    (net (code "58") (name "unconnected-(U1-PB10{slash}USART3_Tx{slash}I2C2_SCL{slash}T2C3-Pad21)") (class "Default")
      (node (ref "U1") (pin "21") (pinfunction "PB10/USART3_Tx/I2C2_SCL/T2C3_21") (pintype "passive"))
    )
    (net (code "59") (name "unconnected-(U1-PB11{slash}USART3_Rx{slash}I2C2_SDA{slash}T2C4-Pad22)") (class "Default")
      (node (ref "U1") (pin "22") (pinfunction "PB11/USART3_Rx/I2C2_SDA/T2C4_22") (pintype "passive"))
    )
    (net (code "60") (name "unconnected-(U1-PC13-TAMPER-RTC-Pad2)") (class "Default")
      (node (ref "U1") (pin "2") (pinfunction "PC13-TAMPER-RTC_2") (pintype "passive"))
    )
    (net (code "61") (name "unconnected-(Y1-Pad3)") (class "Default")
      (node (ref "Y1") (pin "3") (pinfunction "3_3") (pintype "passive"))
    )
  )
)
